# main.net
KiCad netlist of a schematic drawn in Altium Designer
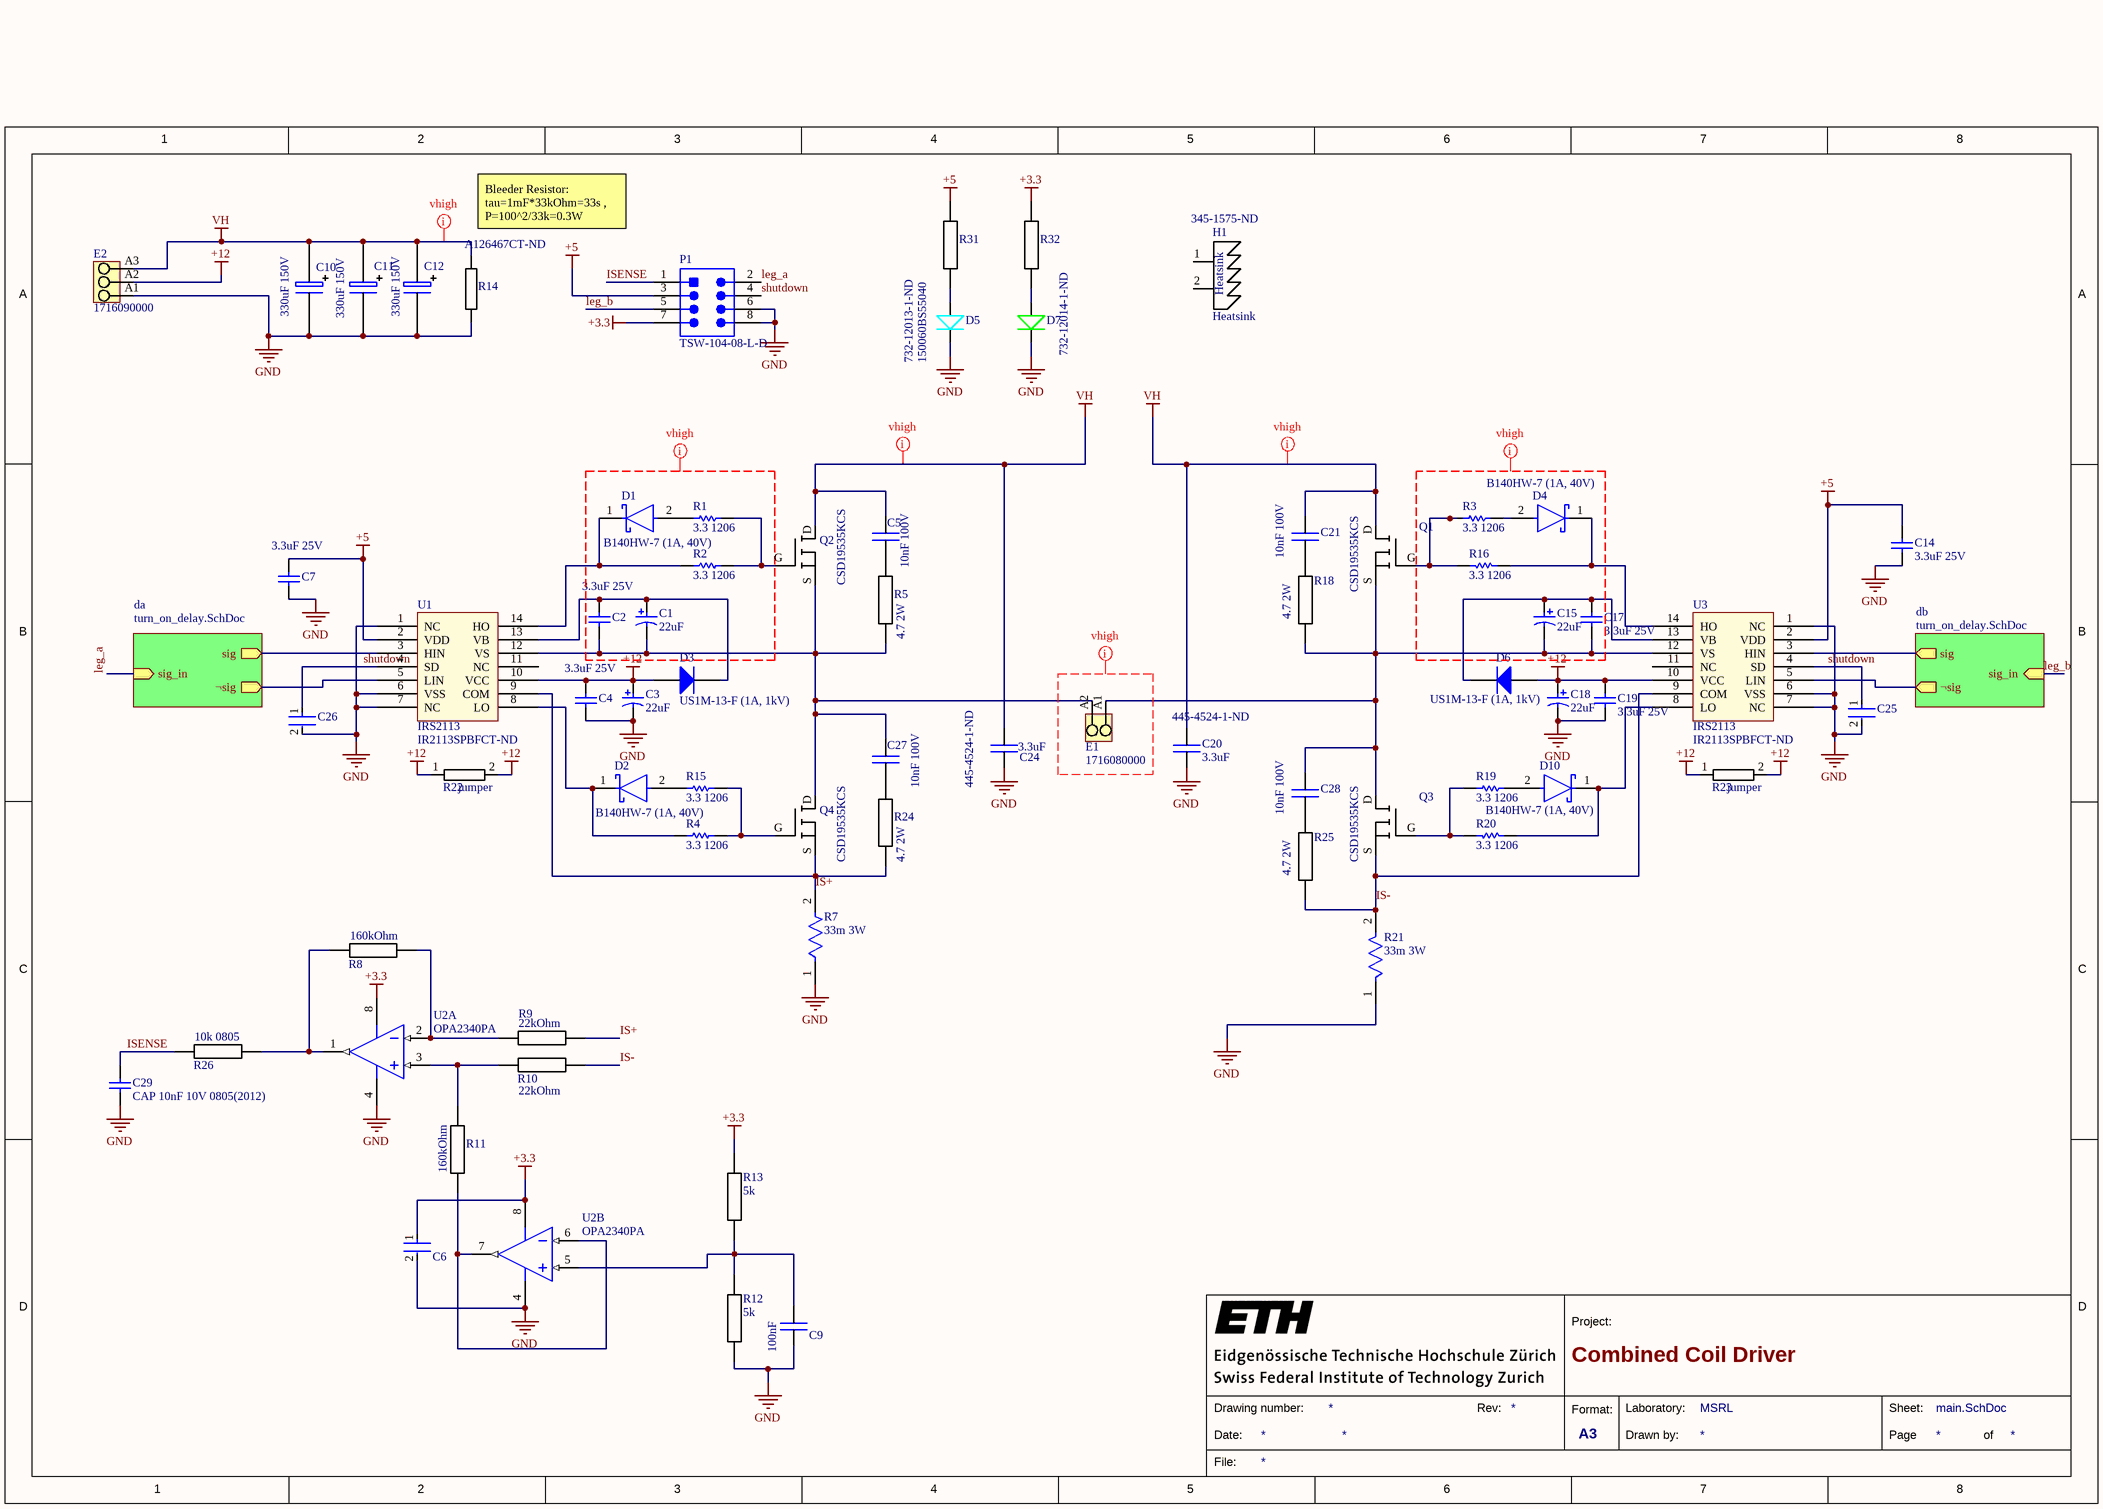
[diagram p0: main.SchDoc]

(export (version "E")
  (design (tool "Eeschema 10.0.6"))
  (components
    (comp (ref "C1")
      (value "22uF")
      (footprint "KEMT-D-7343-31-2_L")
      (description "Capacitor, Tantalum, 22 uF, +/- 10%, 35 V, -55 to 125 degC, 2-Pin Molded, RoHS, Tape and Reel")
      (fields (field (name "VOLTAGE") "35VDC") (field (name "MANUFACTURER") "Kemet"))
      (libsource (lib "Altium Content Vault") (part "CAP-P-2"))
    )
    (comp (ref "C2")
      (value "3.3uF 25V")
      (footprint "CAPC1210(3225)170_M")
      (description "CAP 3.3uF 25V ±10% 1210 (3225 Metric) Thickness 1.7mm SMD")
      (fields (field (name "TOLERANCE") "Â±10%"))
      (libsource (lib "Altium Content Vault") (part "CAP"))
    )
    (comp (ref "C3")
      (value "22uF")
      (footprint "KEMT-D-7343-31-2_L")
      (description "Capacitor, Tantalum, 22 uF, +/- 10%, 35 V, -55 to 125 degC, 2-Pin Molded, RoHS, Tape and Reel")
      (fields (field (name "VOLTAGE") "35VDC") (field (name "MANUFACTURER") "Kemet"))
      (libsource (lib "Altium Content Vault") (part "CAP-P-2"))
    )
    (comp (ref "C4")
      (value "3.3uF 25V")
      (footprint "CAPC1210(3225)170_M")
      (description "CAP 3.3uF 25V ±10% 1210 (3225 Metric) Thickness 1.7mm SMD")
      (fields (field (name "TOLERANCE") "Â±10%"))
      (libsource (lib "Altium Content Vault") (part "CAP"))
    )
    (comp (ref "C5")
      (value "10nF 100V")
      (footprint "1206")
      (libsource (lib "coil_driver_lib") (part "cap_smd"))
    )
    (comp (ref "C6")
      (value "C0603X104K5RACTU")
      (footprint "FP-C0603-CJ-MFG")
      (description "CAP CER 0.1UF 50V X7R 0603")
      (fields (field (name "VOLTAGE") "50V") (field (name "MANUFACTURER") "Kemet"))
      (libsource (lib "Altium Content Vault") (part "11868f565c42a9108669ba33697ecf6"))
    )
    (comp (ref "C7")
      (value "3.3uF 25V")
      (footprint "CAPC1210(3225)170_M")
      (description "CAP 3.3uF 25V ±10% 1210 (3225 Metric) Thickness 1.7mm SMD")
      (fields (field (name "TOLERANCE") "Â±10%"))
      (libsource (lib "Altium Content Vault") (part "CAP"))
    )
    (comp (ref "C9") (value "100nF") (footprint "0805") (libsource (lib "coil_driver_lib") (part "cap_smd")))
    (comp (ref "C10")
      (value "330uF 150V")
      (footprint "cap_electrolyte")
      (fields (field (name "PARTNO") "UCS2C151MHD1TN"))
      (libsource (lib "coil_driver_lib") (part "cap_electrolyte"))
    )
    (comp (ref "C11")
      (value "330uF 150V")
      (footprint "cap_electrolyte")
      (fields (field (name "PARTNO") "UCS2C151MHD1TN"))
      (libsource (lib "coil_driver_lib") (part "cap_electrolyte"))
    )
    (comp (ref "C12")
      (value "330uF 150V")
      (footprint "cap_electrolyte")
      (fields (field (name "PARTNO") "UCS2C151MHD1TN"))
      (libsource (lib "coil_driver_lib") (part "cap_electrolyte"))
    )
    (comp (ref "C14")
      (value "3.3uF 25V")
      (footprint "CAPC1210(3225)170_M")
      (description "CAP 3.3uF 25V ±10% 1210 (3225 Metric) Thickness 1.7mm SMD")
      (fields (field (name "TOLERANCE") "Â±10%"))
      (libsource (lib "Altium Content Vault") (part "CAP"))
    )
    (comp (ref "C15")
      (value "22uF")
      (footprint "KEMT-D-7343-31-2_L")
      (description "Capacitor, Tantalum, 22 uF, +/- 10%, 35 V, -55 to 125 degC, 2-Pin Molded, RoHS, Tape and Reel")
      (fields (field (name "VOLTAGE") "35VDC") (field (name "MANUFACTURER") "Kemet"))
      (libsource (lib "") (part "CAP-P-2_1"))
    )
    (comp (ref "C17")
      (value "3.3uF 25V")
      (footprint "CAPC1210(3225)170_M")
      (description "CAP 3.3uF 25V ±10% 1210 (3225 Metric) Thickness 1.7mm SMD")
      (fields (field (name "TOLERANCE") "Â±10%"))
      (libsource (lib "Altium Content Vault") (part "CAP"))
    )
    (comp (ref "C18")
      (value "22uF")
      (footprint "KEMT-D-7343-31-2_L")
      (description "Capacitor, Tantalum, 22 uF, +/- 10%, 35 V, -55 to 125 degC, 2-Pin Molded, RoHS, Tape and Reel")
      (fields (field (name "VOLTAGE") "35VDC") (field (name "MANUFACTURER") "Kemet"))
      (libsource (lib "") (part "CAP-P-2_1"))
    )
    (comp (ref "C19")
      (value "3.3uF 25V")
      (footprint "CAPC1210(3225)170_M")
      (description "CAP 3.3uF 25V ±10% 1210 (3225 Metric) Thickness 1.7mm SMD")
      (fields (field (name "TOLERANCE") "Â±10%"))
      (libsource (lib "Altium Content Vault") (part "CAP"))
    )
    (comp (ref "C20")
      (value "3.3uF")
      (footprint "SMD_5750")
      (fields (field (name "SUPPLIER PART NUMBER 1") "445-4524-1-ND"))
      (libsource (lib "coil_driver_lib") (part "cap_smd"))
    )
    (comp (ref "C21")
      (value "10nF 100V")
      (footprint "1206")
      (libsource (lib "coil_driver_lib") (part "cap_smd"))
    )
    (comp (ref "C24")
      (value "3.3uF")
      (footprint "SMD_5750")
      (fields (field (name "SUPPLIER PART NUMBER 1") "445-4524-1-ND"))
      (libsource (lib "coil_driver_lib") (part "cap_smd"))
    )
    (comp (ref "C25")
      (value "CC0603KRX7R9BB103")
      (footprint "FP-CC0603-DA-MFG")
      (description "CAP CER 10000PF 50V X7R 0603")
      (fields (field (name "TOLERANCE") "0.1") (field (name "MANUFACTURER") "YAGEO"))
      (libsource (lib "Altium Content Vault") (part "11868f565c42a9108669ba33697ecf6"))
    )
    (comp (ref "C26")
      (value "CC0603KRX7R9BB103")
      (footprint "FP-CC0603-DA-MFG")
      (description "CAP CER 10000PF 50V X7R 0603")
      (fields (field (name "TOLERANCE") "0.1") (field (name "MANUFACTURER") "YAGEO"))
      (libsource (lib "Altium Content Vault") (part "11868f565c42a9108669ba33697ecf6"))
    )
    (comp (ref "C27")
      (value "10nF 100V")
      (footprint "1206")
      (libsource (lib "coil_driver_lib") (part "cap_smd"))
    )
    (comp (ref "C28")
      (value "10nF 100V")
      (footprint "1206")
      (libsource (lib "coil_driver_lib") (part "cap_smd"))
    )
    (comp (ref "C29")
      (value "CAP 10nF 10V 0805(2012)")
      (footprint "CAPC0805(2012)100_N")
      (description "CAP 10nF 10V ±5% 0805 (2012 Metric) Thickness 1mm SMD")
      (fields (field (name "TOLERANCE") "Â±5%"))
      (libsource (lib "Altium Content Vault") (part "CAP"))
    )
    (comp (ref "D1")
      (value "B140HW-7 (1A, 40V)")
      (footprint "FP-SOD123-MFG")
      (fields
        (field (name "MANUFACTURER") "Diodes Inc.")
        (field (name "OCTOPART") "https://octopart.com/b140hw-7-diodes+inc.-325751")
        (field (name "MANUFACTURER PART NUMBER") "B140HW-7")
      )
      (libsource (lib "Altium Content Vault") (part "1d6ec82d83fb6aee721767c19dac4b9"))
    )
    (comp (ref "D2")
      (value "B140HW-7 (1A, 40V)")
      (footprint "FP-SOD123-MFG")
      (description "DIODE SCHOTTKY 40V 1A SOD123 Alternative: 1655-2275-1-ND - Cut Tape (CT)")
      (fields
        (field (name "MANUFACTURER") "Diodes Inc.")
        (field (name "OCTOPART") "https://octopart.com/b140hw-7-diodes+inc.-325751")
      )
      (libsource (lib "Altium Content Vault") (part "1d6ec82d83fb6aee721767c19dac4b9"))
    )
    (comp (ref "D3")
      (value "US1M-13-F (1A, 1kV)")
      (footprint "DIOD-SMA-2_A_V")
      (description "Ultra-Fast Rectifier, 1 A, 1.7 V, -65 to 150 degC, 2-Pin SMA, RoHS, Tape and Reel")
      (fields (field (name "MANUFACTURER") "Diodes Inc"))
      (libsource (lib "Altium Content Vault") (part "D-AK-2"))
    )
    (comp (ref "D4")
      (value "B140HW-7 (1A, 40V)")
      (footprint "FP-SOD123-MFG")
      (description "DIODE SCHOTTKY 40V 1A SOD123 Alternative: 1655-2275-1-ND - Cut Tape (CT)")
      (fields
        (field (name "MANUFACTURER") "Diodes Inc.")
        (field (name "OCTOPART") "https://octopart.com/b140hw-7-diodes+inc.-325751")
      )
      (libsource (lib "Altium Content Vault") (part "1d6ec82d83fb6aee721767c19dac4b9"))
    )
    (comp (ref "D5")
      (value "150060BS55040")
      (footprint "LED_BLUE_0603")
      (fields (field (name "SUPPLIER PART NUMBER 1") "732-12013-1-ND"))
      (libsource (lib "coil_driver_lib") (part "led_blue_0603"))
    )
    (comp (ref "D6")
      (value "US1M-13-F (1A, 1kV)")
      (footprint "DIOD-SMA-2_A_V")
      (description "Ultra-Fast Rectifier, 1 A, 1.7 V, -65 to 150 degC, 2-Pin SMA, RoHS, Tape and Reel")
      (fields (field (name "MANUFACTURER") "Diodes Inc"))
      (libsource (lib "Altium Content Vault") (part "D-AK-2"))
    )
    (comp (ref "D7")
      (value "732-12014-1-ND")
      (footprint "LED_GREEN_0603")
      (fields (field (name "SUPPLIER PART NUMBER 1") "732-12014-1-ND"))
      (libsource (lib "coil_driver_lib") (part "led_green_0603"))
    )
    (comp (ref "D10")
      (value "B140HW-7 (1A, 40V)")
      (footprint "FP-SOD123-MFG")
      (description "DIODE SCHOTTKY 40V 1A SOD123 Alternative: 1655-2275-1-ND - Cut Tape (CT)")
      (fields
        (field (name "MANUFACTURER") "Diodes Inc.")
        (field (name "OCTOPART") "https://octopart.com/b140hw-7-diodes+inc.-325751")
      )
      (libsource (lib "Altium Content Vault") (part "1d6ec82d83fb6aee721767c19dac4b9"))
    )
    (comp (ref "E1")
      (value "1716080000")
      (footprint "LM_5_08_90_02")
      (description "OMNIMATE Signal - series LM")
      (fields (field (name "MANUFACTURER") "Weidmueller"))
      (libsource (lib "Altium Content Vault") (part "Terminal_02_1x02"))
    )
    (comp (ref "E2")
      (value "1716090000")
      (footprint "LM_5_08_90_03")
      (description "OMNIMATE Signal - series LM")
      (fields (field (name "MANUFACTURER") "Weidmueller"))
      (libsource (lib "Altium Content Vault") (part "Terminal_03_1x03"))
    )
    (comp (ref "H1")
      (value "Heatsink")
      (footprint "omni-uni-30-75-d")
      (fields (field (name "SUPPLIER PART NUMBER 1") "345-1575-ND"))
      (libsource (lib "coil_driver_lib") (part "Heatsink"))
    )
    (comp (ref "P1")
      (value "TSW-104-08-L-D")
      (footprint "SMTC-TSW-104-08-L-D_V")
      (fields (field (name "MANUFACTURER") "Samtec"))
      (libsource (lib "Altium Content Vault") (part "CN-2P-M-R8"))
    )
    (comp (ref "Q1")
      (value "CSD19535KCS")
      (footprint "TO-220")
      (libsource (lib "coil_driver_lib") (part "CSD19535KCS"))
    )
    (comp (ref "Q2")
      (value "CSD19535KCS")
      (footprint "TO-220")
      (libsource (lib "coil_driver_lib") (part "CSD19535KCS"))
    )
    (comp (ref "Q3")
      (value "CSD19535KCS")
      (footprint "TO-220")
      (libsource (lib "coil_driver_lib") (part "CSD19535KCS"))
    )
    (comp (ref "Q4")
      (value "CSD19535KCS")
      (footprint "TO-220")
      (libsource (lib "coil_driver_lib") (part "CSD19535KCS"))
    )
    (comp (ref "R1")
      (value "3.3 1206")
      (footprint "RESC3216X70X50LL05T20")
      (fields (field (name "PART NUMBER") "ERJ-8RQF3R3V") (field (name "MANUFACTURER") "Panasonic"))
      (libsource (lib "Altium Content Vault") (part "RES"))
    )
    (comp (ref "R2")
      (value "3.3 1206")
      (footprint "RESC3216X70X50LL05T20")
      (fields (field (name "PART NUMBER") "ERJ-8RQF3R3V") (field (name "MANUFACTURER") "Panasonic"))
      (libsource (lib "Altium Content Vault") (part "RES"))
    )
    (comp (ref "R3")
      (value "3.3 1206")
      (footprint "RESC3216X70X50LL05T20")
      (fields (field (name "PART NUMBER") "ERJ-8RQF3R3V") (field (name "MANUFACTURER") "Panasonic"))
      (libsource (lib "Altium Content Vault") (part "RES"))
    )
    (comp (ref "R4")
      (value "3.3 1206")
      (footprint "RESC3216X70X50LL05T20")
      (fields (field (name "PART NUMBER") "ERJ-8RQF3R3V") (field (name "MANUFACTURER") "Panasonic"))
      (libsource (lib "Altium Content Vault") (part "RES"))
    )
    (comp (ref "R5") (value "4.7 2W") (footprint "2512") (libsource (lib "coil_driver_lib") (part "res_smd")))
    (comp (ref "R7")
      (value "33m 3W")
      (footprint "FP-KRL6432E-M-R033-F-T1-MFG")
      (description "RES 0.033 OHM 3W 2512 WIDE")
      (fields
        (field (name "OCTOPART") "https://octopart.com/krl6432e-m-r033-f-t1-susumu-24927468")
        (field (name "MANUFACTURER PART NUMBER") "KRL6432E-M-R033-F-T1")
      )
      (libsource (lib "Altium Content Vault") (part "1029c3af85768c4190bb7ad29bc67b5"))
    )
    (comp (ref "R8")
      (value "160kOhm")
      (footprint "0805")
      (libsource (lib "coil_driver_lib") (part "res_smd"))
    )
    (comp (ref "R9") (value "22kOhm") (footprint "0805") (libsource (lib "coil_driver_lib") (part "res_smd")))
    (comp (ref "R10")
      (value "22kOhm")
      (footprint "0805")
      (libsource (lib "coil_driver_lib") (part "res_smd"))
    )
    (comp (ref "R11")
      (value "160kOhm")
      (footprint "0805")
      (libsource (lib "coil_driver_lib") (part "res_smd"))
    )
    (comp (ref "R12") (value "5k") (footprint "0805") (libsource (lib "coil_driver_lib") (part "res_smd")))
    (comp (ref "R13") (value "5k") (footprint "0805") (libsource (lib "coil_driver_lib") (part "res_smd")))
    (comp (ref "R14")
      (value "CRGH2512J33K")
      (footprint "res_bleeder")
      (description "33kOhm 2W")
      (fields (field (name "SUPPLIER PART NUMBER 1") "A126467CT-ND"))
      (libsource (lib "coil_driver_lib") (part "res_bleeder"))
    )
    (comp (ref "R15")
      (value "3.3 1206")
      (footprint "RESC3216X70X50LL05T20")
      (fields (field (name "PART NUMBER") "ERJ-8RQF3R3V") (field (name "MANUFACTURER") "Panasonic"))
      (libsource (lib "Altium Content Vault") (part "RES"))
    )
    (comp (ref "R16")
      (value "3.3 1206")
      (footprint "RESC3216X70X50LL05T20")
      (fields (field (name "PART NUMBER") "ERJ-8RQF3R3V") (field (name "MANUFACTURER") "Panasonic"))
      (libsource (lib "Altium Content Vault") (part "RES"))
    )
    (comp (ref "R18")
      (value "4.7 2W")
      (footprint "2512")
      (libsource (lib "coil_driver_lib") (part "res_smd"))
    )
    (comp (ref "R19")
      (value "3.3 1206")
      (footprint "RESC3216X70X50LL05T20")
      (fields (field (name "PART NUMBER") "ERJ-8RQF3R3V") (field (name "MANUFACTURER") "Panasonic"))
      (libsource (lib "Altium Content Vault") (part "RES"))
    )
    (comp (ref "R20")
      (value "3.3 1206")
      (footprint "RESC3216X70X50LL05T20")
      (fields (field (name "PART NUMBER") "ERJ-8RQF3R3V") (field (name "MANUFACTURER") "Panasonic"))
      (libsource (lib "Altium Content Vault") (part "RES"))
    )
    (comp (ref "R21")
      (value "33m 3W")
      (footprint "FP-KRL6432E-M-R033-F-T1-MFG")
      (description "RES 0.033 OHM 3W 2512 WIDE")
      (fields
        (field (name "OCTOPART") "https://octopart.com/krl6432e-m-r033-f-t1-susumu-24927468")
        (field (name "MANUFACTURER PART NUMBER") "KRL6432E-M-R033-F-T1")
      )
      (libsource (lib "Altium Content Vault") (part "1029c3af85768c4190bb7ad29bc67b5"))
    )
    (comp (ref "R22")
      (value "jumper")
      (footprint "tht_resistor_10mm")
      (libsource (lib "coil_driver_lib") (part "res_th"))
    )
    (comp (ref "R23")
      (value "jumper")
      (footprint "tht_resistor_10mm")
      (libsource (lib "coil_driver_lib") (part "res_th"))
    )
    (comp (ref "R24")
      (value "4.7 2W")
      (footprint "2512")
      (libsource (lib "coil_driver_lib") (part "res_smd"))
    )
    (comp (ref "R25")
      (value "4.7 2W")
      (footprint "2512")
      (libsource (lib "coil_driver_lib") (part "res_smd"))
    )
    (comp (ref "R26")
      (value "10k 0805")
      (footprint "0805")
      (libsource (lib "coil_driver_lib") (part "res_smd"))
    )
    (comp (ref "R31")
      (value "res_smd")
      (footprint "0805")
      (libsource (lib "coil_driver_lib") (part "res_smd"))
    )
    (comp (ref "R32")
      (value "res_smd")
      (footprint "0805")
      (libsource (lib "coil_driver_lib") (part "res_smd"))
    )
    (comp (ref "U1")
      (value "IRS2113")
      (footprint "DIP14")
      (fields (field (name "SUPPLIER PART NUMBER 1") "IR2113SPBFCT-ND"))
      (libsource (lib "coil_driver_lib") (part "IR2113"))
    )
    (comp (ref "U2")
      (value "OPA2340PA")
      (footprint "P0008A")
      (fields (field (name "MANUFACTURER") "Texas Instruments"))
      (libsource (lib "Altium Content Vault") (part "TI-OPA-8_2"))
    )
    (comp (ref "U3")
      (value "IRS2113")
      (footprint "DIP14")
      (fields (field (name "SUPPLIER PART NUMBER 1") "IR2113SPBFCT-ND"))
      (libsource (lib "") (part "IR2113_1"))
    )
  )
  (nets
    (net (code "1") (name "+3.3") (class "Default")
      (node (ref "C6") (pin "1") (pinfunction "1_1") (pintype "passive"))
      (node (ref "P1") (pin "7") (pinfunction "7_7") (pintype "passive"))
      (node (ref "R13") (pin "2") (pinfunction "2_2") (pintype "passive"))
      (node (ref "R32") (pin "1") (pinfunction "1_1") (pintype "passive"))
      (node (ref "U2") (pin "8") (pinfunction "V+_8") (pintype "power_in"))
    )
    (net (code "2") (name "+5") (class "Default")
      (node (ref "C14") (pin "2") (pinfunction "2_2") (pintype "passive"))
      (node (ref "C7") (pin "2") (pinfunction "2_2") (pintype "passive"))
      (node (ref "P1") (pin "3") (pinfunction "3_3") (pintype "passive"))
      (node (ref "R31") (pin "1") (pinfunction "1_1") (pintype "passive"))
      (node (ref "U1") (pin "2") (pinfunction "VDD_2") (pintype "passive"))
      (node (ref "U3") (pin "2") (pinfunction "VDD_2") (pintype "passive"))
    )
    (net (code "3") (name "+12") (class "Default")
      (node (ref "C18") (pin "1") (pinfunction "1_1") (pintype "passive"))
      (node (ref "C19") (pin "2") (pinfunction "2_2") (pintype "passive"))
      (node (ref "C3") (pin "1") (pinfunction "1_1") (pintype "passive"))
      (node (ref "C4") (pin "2") (pinfunction "2_2") (pintype "passive"))
      (node (ref "D3") (pin "1") (pinfunction "A_1") (pintype "passive"))
      (node (ref "D6") (pin "1") (pinfunction "A_1") (pintype "passive"))
      (node (ref "E2") (pin "A2") (pinfunction "A2_A2") (pintype "passive"))
      (node (ref "R22") (pin "1") (pinfunction "1_1") (pintype "passive"))
      (node (ref "R22") (pin "2") (pinfunction "2_2") (pintype "passive"))
      (node (ref "R23") (pin "1") (pinfunction "1_1") (pintype "passive"))
      (node (ref "R23") (pin "2") (pinfunction "2_2") (pintype "passive"))
      (node (ref "U1") (pin "10") (pinfunction "VCC_10") (pintype "passive"))
      (node (ref "U3") (pin "10") (pinfunction "VCC_10") (pintype "passive"))
    )
    (net (code "4") (name "/IS+") (class "Default")
      (node (ref "Q4") (pin "S") (pinfunction "S_S") (pintype "passive"))
      (node (ref "R24") (pin "2") (pinfunction "2_2") (pintype "passive"))
      (node (ref "R7") (pin "2") (pinfunction "2_2") (pintype "passive"))
      (node (ref "R9") (pin "2") (pinfunction "2_2") (pintype "passive"))
      (node (ref "U1") (pin "9") (pinfunction "COM_9") (pintype "passive"))
    )
    (net (code "5") (name "/IS-") (class "Default")
      (node (ref "Q3") (pin "S") (pinfunction "S_S") (pintype "passive"))
      (node (ref "R10") (pin "2") (pinfunction "2_2") (pintype "passive"))
      (node (ref "R21") (pin "2") (pinfunction "2_2") (pintype "passive"))
      (node (ref "R25") (pin "2") (pinfunction "2_2") (pintype "passive"))
      (node (ref "U3") (pin "9") (pinfunction "COM_9") (pintype "passive"))
    )
    (net (code "6") (name "/ISENSE") (class "Default")
      (node (ref "C29") (pin "2") (pinfunction "2_2") (pintype "passive"))
      (node (ref "P1") (pin "1") (pinfunction "1_1") (pintype "passive"))
      (node (ref "R26") (pin "1") (pinfunction "1_1") (pintype "passive"))
    )
    (net (code "7") (name "/leg_a") (class "Default")
      (node (ref "P1") (pin "2") (pinfunction "2_2") (pintype "passive"))
    )
    (net (code "8") (name "/leg_b") (class "Default")
      (node (ref "P1") (pin "5") (pinfunction "5_5") (pintype "passive"))
    )
    (net (code "9") (name "/shutdown") (class "Default")
      (node (ref "C25") (pin "1") (pinfunction "1_1") (pintype "passive"))
      (node (ref "C26") (pin "1") (pinfunction "1_1") (pintype "passive"))
      (node (ref "P1") (pin "4") (pinfunction "4_4") (pintype "passive"))
      (node (ref "U1") (pin "4") (pinfunction "SD_4") (pintype "passive"))
      (node (ref "U3") (pin "4") (pinfunction "SD_4") (pintype "passive"))
    )
    (net (code "10") (name "/sig") (class "Default")
      (node (ref "U1") (pin "3") (pinfunction "HIN_3") (pintype "passive"))
    )
    (net (code "11") (name "/sig_1") (class "Default")
      (node (ref "U3") (pin "3") (pinfunction "HIN_3") (pintype "passive"))
    )
    (net (code "12") (name "/¬sig") (class "Default")
      (node (ref "U1") (pin "5") (pinfunction "LIN_5") (pintype "passive"))
    )
    (net (code "13") (name "/¬sig_1") (class "Default")
      (node (ref "U3") (pin "5") (pinfunction "LIN_5") (pintype "passive"))
    )
    (net (code "14") (name "GND") (class "Default")
      (node (ref "C10") (pin "2") (pinfunction "2_2") (pintype "passive"))
      (node (ref "C11") (pin "2") (pinfunction "2_2") (pintype "passive"))
      (node (ref "C12") (pin "2") (pinfunction "2_2") (pintype "passive"))
      (node (ref "C14") (pin "1") (pinfunction "1_1") (pintype "passive"))
      (node (ref "C18") (pin "2") (pinfunction "2_2") (pintype "passive"))
      (node (ref "C19") (pin "1") (pinfunction "1_1") (pintype "passive"))
      (node (ref "C20") (pin "2") (pinfunction "2_2") (pintype "passive"))
      (node (ref "C24") (pin "2") (pinfunction "2_2") (pintype "passive"))
      (node (ref "C25") (pin "2") (pinfunction "2_2") (pintype "passive"))
      (node (ref "C26") (pin "2") (pinfunction "2_2") (pintype "passive"))
      (node (ref "C29") (pin "1") (pinfunction "1_1") (pintype "passive"))
      (node (ref "C3") (pin "2") (pinfunction "2_2") (pintype "passive"))
      (node (ref "C4") (pin "1") (pinfunction "1_1") (pintype "passive"))
      (node (ref "C6") (pin "2") (pinfunction "2_2") (pintype "passive"))
      (node (ref "C7") (pin "1") (pinfunction "1_1") (pintype "passive"))
      (node (ref "C9") (pin "2") (pinfunction "2_2") (pintype "passive"))
      (node (ref "D5") (pin "K") (pinfunction "K_K") (pintype "passive"))
      (node (ref "D7") (pin "K") (pinfunction "K_K") (pintype "passive"))
      (node (ref "E2") (pin "A1") (pinfunction "A1_A1") (pintype "passive"))
      (node (ref "P1") (pin "6") (pinfunction "6_6") (pintype "passive"))
      (node (ref "P1") (pin "8") (pinfunction "8_8") (pintype "passive"))
      (node (ref "R12") (pin "1") (pinfunction "1_1") (pintype "passive"))
      (node (ref "R14") (pin "1") (pinfunction "1_1") (pintype "passive"))
      (node (ref "R21") (pin "1") (pinfunction "1_1") (pintype "passive"))
      (node (ref "R7") (pin "1") (pinfunction "1_1") (pintype "passive"))
      (node (ref "U1") (pin "1") (pinfunction "NC_1") (pintype "passive"))
      (node (ref "U1") (pin "6") (pinfunction "VSS_6") (pintype "passive"))
      (node (ref "U1") (pin "7") (pinfunction "NC_7") (pintype "passive"))
      (node (ref "U2") (pin "4") (pinfunction "V-_4") (pintype "power_in"))
      (node (ref "U3") (pin "1") (pinfunction "NC_1") (pintype "passive"))
      (node (ref "U3") (pin "6") (pinfunction "VSS_6") (pintype "passive"))
      (node (ref "U3") (pin "7") (pinfunction "NC_7") (pintype "passive"))
    )
    (net (code "15") (name "Net-(C5-Pad2)") (class "Default")
      (node (ref "C5") (pin "2") (pinfunction "2_2") (pintype "passive"))
      (node (ref "R5") (pin "1") (pinfunction "1_1") (pintype "passive"))
    )
    (net (code "16") (name "Net-(C21-Pad2)") (class "Default")
      (node (ref "C21") (pin "2") (pinfunction "2_2") (pintype "passive"))
      (node (ref "R18") (pin "1") (pinfunction "1_1") (pintype "passive"))
    )
    (net (code "17") (name "Net-(C27-Pad2)") (class "Default")
      (node (ref "C27") (pin "2") (pinfunction "2_2") (pintype "passive"))
      (node (ref "R24") (pin "1") (pinfunction "1_1") (pintype "passive"))
    )
    (net (code "18") (name "Net-(C28-Pad2)") (class "Default")
      (node (ref "C28") (pin "2") (pinfunction "2_2") (pintype "passive"))
      (node (ref "R25") (pin "1") (pinfunction "1_1") (pintype "passive"))
    )
    (net (code "19") (name "Net-(D1-A)") (class "Default")
      (node (ref "D1") (pin "2") (pinfunction "A_2") (pintype "passive"))
      (node (ref "R1") (pin "1") (pinfunction "1_1") (pintype "passive"))
    )
    (net (code "20") (name "Net-(D1-C)") (class "Default")
      (node (ref "D1") (pin "1") (pinfunction "C_1") (pintype "passive"))
      (node (ref "R2") (pin "1") (pinfunction "1_1") (pintype "passive"))
      (node (ref "U1") (pin "14") (pinfunction "HO_14") (pintype "passive"))
    )
    (net (code "21") (name "Net-(D2-A)") (class "Default")
      (node (ref "D2") (pin "2") (pinfunction "A_2") (pintype "passive"))
      (node (ref "R15") (pin "1") (pinfunction "1_1") (pintype "passive"))
    )
    (net (code "22") (name "Net-(D2-C)") (class "Default")
      (node (ref "D2") (pin "1") (pinfunction "C_1") (pintype "passive"))
      (node (ref "R4") (pin "1") (pinfunction "1_1") (pintype "passive"))
      (node (ref "U1") (pin "8") (pinfunction "LO_8") (pintype "passive"))
    )
    (net (code "23") (name "Net-(D3-K)") (class "Default")
      (node (ref "C1") (pin "1") (pinfunction "1_1") (pintype "passive"))
      (node (ref "C2") (pin "2") (pinfunction "2_2") (pintype "passive"))
      (node (ref "D3") (pin "2") (pinfunction "K_2") (pintype "passive"))
      (node (ref "U1") (pin "13") (pinfunction "VB_13") (pintype "passive"))
    )
    (net (code "24") (name "Net-(D4-A)") (class "Default")
      (node (ref "D4") (pin "2") (pinfunction "A_2") (pintype "passive"))
      (node (ref "R3") (pin "2") (pinfunction "2_2") (pintype "passive"))
    )
    (net (code "25") (name "Net-(D4-C)") (class "Default")
      (node (ref "D4") (pin "1") (pinfunction "C_1") (pintype "passive"))
      (node (ref "R16") (pin "1") (pinfunction "1_1") (pintype "passive"))
      (node (ref "U3") (pin "14") (pinfunction "HO_14") (pintype "passive"))
    )
    (net (code "26") (name "Net-(D5-PadA)") (class "Default")
      (node (ref "D5") (pin "A") (pinfunction "A_A") (pintype "passive"))
      (node (ref "R31") (pin "2") (pinfunction "2_2") (pintype "passive"))
    )
    (net (code "27") (name "Net-(D6-K)") (class "Default")
      (node (ref "C15") (pin "1") (pinfunction "1_1") (pintype "passive"))
      (node (ref "C17") (pin "2") (pinfunction "2_2") (pintype "passive"))
      (node (ref "D6") (pin "2") (pinfunction "K_2") (pintype "passive"))
      (node (ref "U3") (pin "13") (pinfunction "VB_13") (pintype "passive"))
    )
    (net (code "28") (name "Net-(D7-PadA)") (class "Default")
      (node (ref "D7") (pin "A") (pinfunction "A_A") (pintype "passive"))
      (node (ref "R32") (pin "2") (pinfunction "2_2") (pintype "passive"))
    )
    (net (code "29") (name "Net-(D10-A)") (class "Default")
      (node (ref "D10") (pin "2") (pinfunction "A_2") (pintype "passive"))
      (node (ref "R19") (pin "2") (pinfunction "2_2") (pintype "passive"))
    )
    (net (code "30") (name "Net-(D10-C)") (class "Default")
      (node (ref "D10") (pin "1") (pinfunction "C_1") (pintype "passive"))
      (node (ref "R20") (pin "1") (pinfunction "1_1") (pintype "passive"))
      (node (ref "U3") (pin "8") (pinfunction "LO_8") (pintype "passive"))
    )
    (net (code "31") (name "Net-(Q1-PadG)") (class "Default")
      (node (ref "Q1") (pin "G") (pinfunction "G_G") (pintype "passive"))
      (node (ref "R16") (pin "2") (pinfunction "2_2") (pintype "passive"))
      (node (ref "R3") (pin "1") (pinfunction "1_1") (pintype "passive"))
    )
    (net (code "32") (name "Net-(Q2-PadG)") (class "Default")
      (node (ref "Q2") (pin "G") (pinfunction "G_G") (pintype "passive"))
      (node (ref "R1") (pin "2") (pinfunction "2_2") (pintype "passive"))
      (node (ref "R2") (pin "2") (pinfunction "2_2") (pintype "passive"))
    )
    (net (code "33") (name "Net-(Q3-PadG)") (class "Default")
      (node (ref "Q3") (pin "G") (pinfunction "G_G") (pintype "passive"))
      (node (ref "R19") (pin "1") (pinfunction "1_1") (pintype "passive"))
      (node (ref "R20") (pin "2") (pinfunction "2_2") (pintype "passive"))
    )
    (net (code "34") (name "Net-(Q4-PadG)") (class "Default")
      (node (ref "Q4") (pin "G") (pinfunction "G_G") (pintype "passive"))
      (node (ref "R15") (pin "2") (pinfunction "2_2") (pintype "passive"))
      (node (ref "R4") (pin "2") (pinfunction "2_2") (pintype "passive"))
    )
    (net (code "35") (name "Net-(U1-VS)") (class "Default")
      (node (ref "C1") (pin "2") (pinfunction "2_2") (pintype "passive"))
      (node (ref "C2") (pin "1") (pinfunction "1_1") (pintype "passive"))
      (node (ref "C27") (pin "1") (pinfunction "1_1") (pintype "passive"))
      (node (ref "E1") (pin "A2") (pinfunction "A2_A2") (pintype "passive"))
      (node (ref "Q2") (pin "S") (pinfunction "S_S") (pintype "passive"))
      (node (ref "Q4") (pin "D") (pinfunction "D_D") (pintype "passive"))
      (node (ref "R5") (pin "2") (pinfunction "2_2") (pintype "passive"))
      (node (ref "U1") (pin "12") (pinfunction "VS_12") (pintype "passive"))
    )
    (net (code "36") (name "Net-(U2A-IN_A+)") (class "Default")
      (node (ref "R10") (pin "1") (pinfunction "1_1") (pintype "passive"))
      (node (ref "R11") (pin "2") (pinfunction "2_2") (pintype "passive"))
      (node (ref "U2") (pin "3") (pinfunction "IN_A+_3") (pintype "input"))
    )
    (net (code "37") (name "Net-(U2A-IN_A-)") (class "Default")
      (node (ref "R8") (pin "2") (pinfunction "2_2") (pintype "passive"))
      (node (ref "R9") (pin "1") (pinfunction "1_1") (pintype "passive"))
      (node (ref "U2") (pin "2") (pinfunction "IN_A-_2") (pintype "input"))
    )
    (net (code "38") (name "Net-(U2A-OUT_A)") (class "Default")
      (node (ref "R26") (pin "2") (pinfunction "2_2") (pintype "passive"))
      (node (ref "R8") (pin "1") (pinfunction "1_1") (pintype "passive"))
      (node (ref "U2") (pin "1") (pinfunction "OUT_A_1") (pintype "output"))
    )
    (net (code "39") (name "Net-(U2B-IN_B+)") (class "Default")
      (node (ref "C9") (pin "1") (pinfunction "1_1") (pintype "passive"))
      (node (ref "R12") (pin "2") (pinfunction "2_2") (pintype "passive"))
      (node (ref "R13") (pin "1") (pinfunction "1_1") (pintype "passive"))
      (node (ref "U2") (pin "5") (pinfunction "IN_B+_5") (pintype "input"))
    )
    (net (code "40") (name "Net-(U2B-IN_B-)") (class "Default")
      (node (ref "R11") (pin "1") (pinfunction "1_1") (pintype "passive"))
      (node (ref "U2") (pin "6") (pinfunction "IN_B-_6") (pintype "input"))
      (node (ref "U2") (pin "7") (pinfunction "OUT_B_7") (pintype "output"))
    )
    (net (code "41") (name "Net-(U3-VS)") (class "Default")
      (node (ref "C15") (pin "2") (pinfunction "2_2") (pintype "passive"))
      (node (ref "C17") (pin "1") (pinfunction "1_1") (pintype "passive"))
      (node (ref "C28") (pin "1") (pinfunction "1_1") (pintype "passive"))
      (node (ref "E1") (pin "A1") (pinfunction "A1_A1") (pintype "passive"))
      (node (ref "Q1") (pin "S") (pinfunction "S_S") (pintype "passive"))
      (node (ref "Q3") (pin "D") (pinfunction "D_D") (pintype "passive"))
      (node (ref "R18") (pin "2") (pinfunction "2_2") (pintype "passive"))
      (node (ref "U3") (pin "12") (pinfunction "VS_12") (pintype "passive"))
    )
    (net (code "42") (name "VH") (class "Default")
      (node (ref "C10") (pin "1") (pinfunction "1_1") (pintype "passive"))
      (node (ref "C11") (pin "1") (pinfunction "1_1") (pintype "passive"))
      (node (ref "C12") (pin "1") (pinfunction "1_1") (pintype "passive"))
      (node (ref "C20") (pin "1") (pinfunction "1_1") (pintype "passive"))
      (node (ref "C21") (pin "1") (pinfunction "1_1") (pintype "passive"))
      (node (ref "C24") (pin "1") (pinfunction "1_1") (pintype "passive"))
      (node (ref "C5") (pin "1") (pinfunction "1_1") (pintype "passive"))
      (node (ref "E2") (pin "A3") (pinfunction "A3_A3") (pintype "passive"))
      (node (ref "Q1") (pin "D") (pinfunction "D_D") (pintype "passive"))
      (node (ref "Q2") (pin "D") (pinfunction "D_D") (pintype "passive"))
      (node (ref "R14") (pin "2") (pinfunction "2_2") (pintype "passive"))
    )
    (net (code "43") (name "unconnected-(H1-0-Pad1)") (class "Default")
      (node (ref "H1") (pin "1") (pinfunction "0_1") (pintype "passive"))
    )
    (net (code "44") (name "unconnected-(H1-1-Pad2)") (class "Default")
      (node (ref "H1") (pin "2") (pinfunction "1_2") (pintype "passive"))
    )
    (net (code "45") (name "unconnected-(U1-NC-Pad11)") (class "Default")
      (node (ref "U1") (pin "11") (pinfunction "NC_11") (pintype "passive"))
    )
    (net (code "46") (name "unconnected-(U3-NC-Pad11)") (class "Default")
      (node (ref "U3") (pin "11") (pinfunction "NC_11") (pintype "passive"))
    )
  )
)
